# bmsMaster_main.net
KiCad netlist of a schematic drawn in Altium Designer
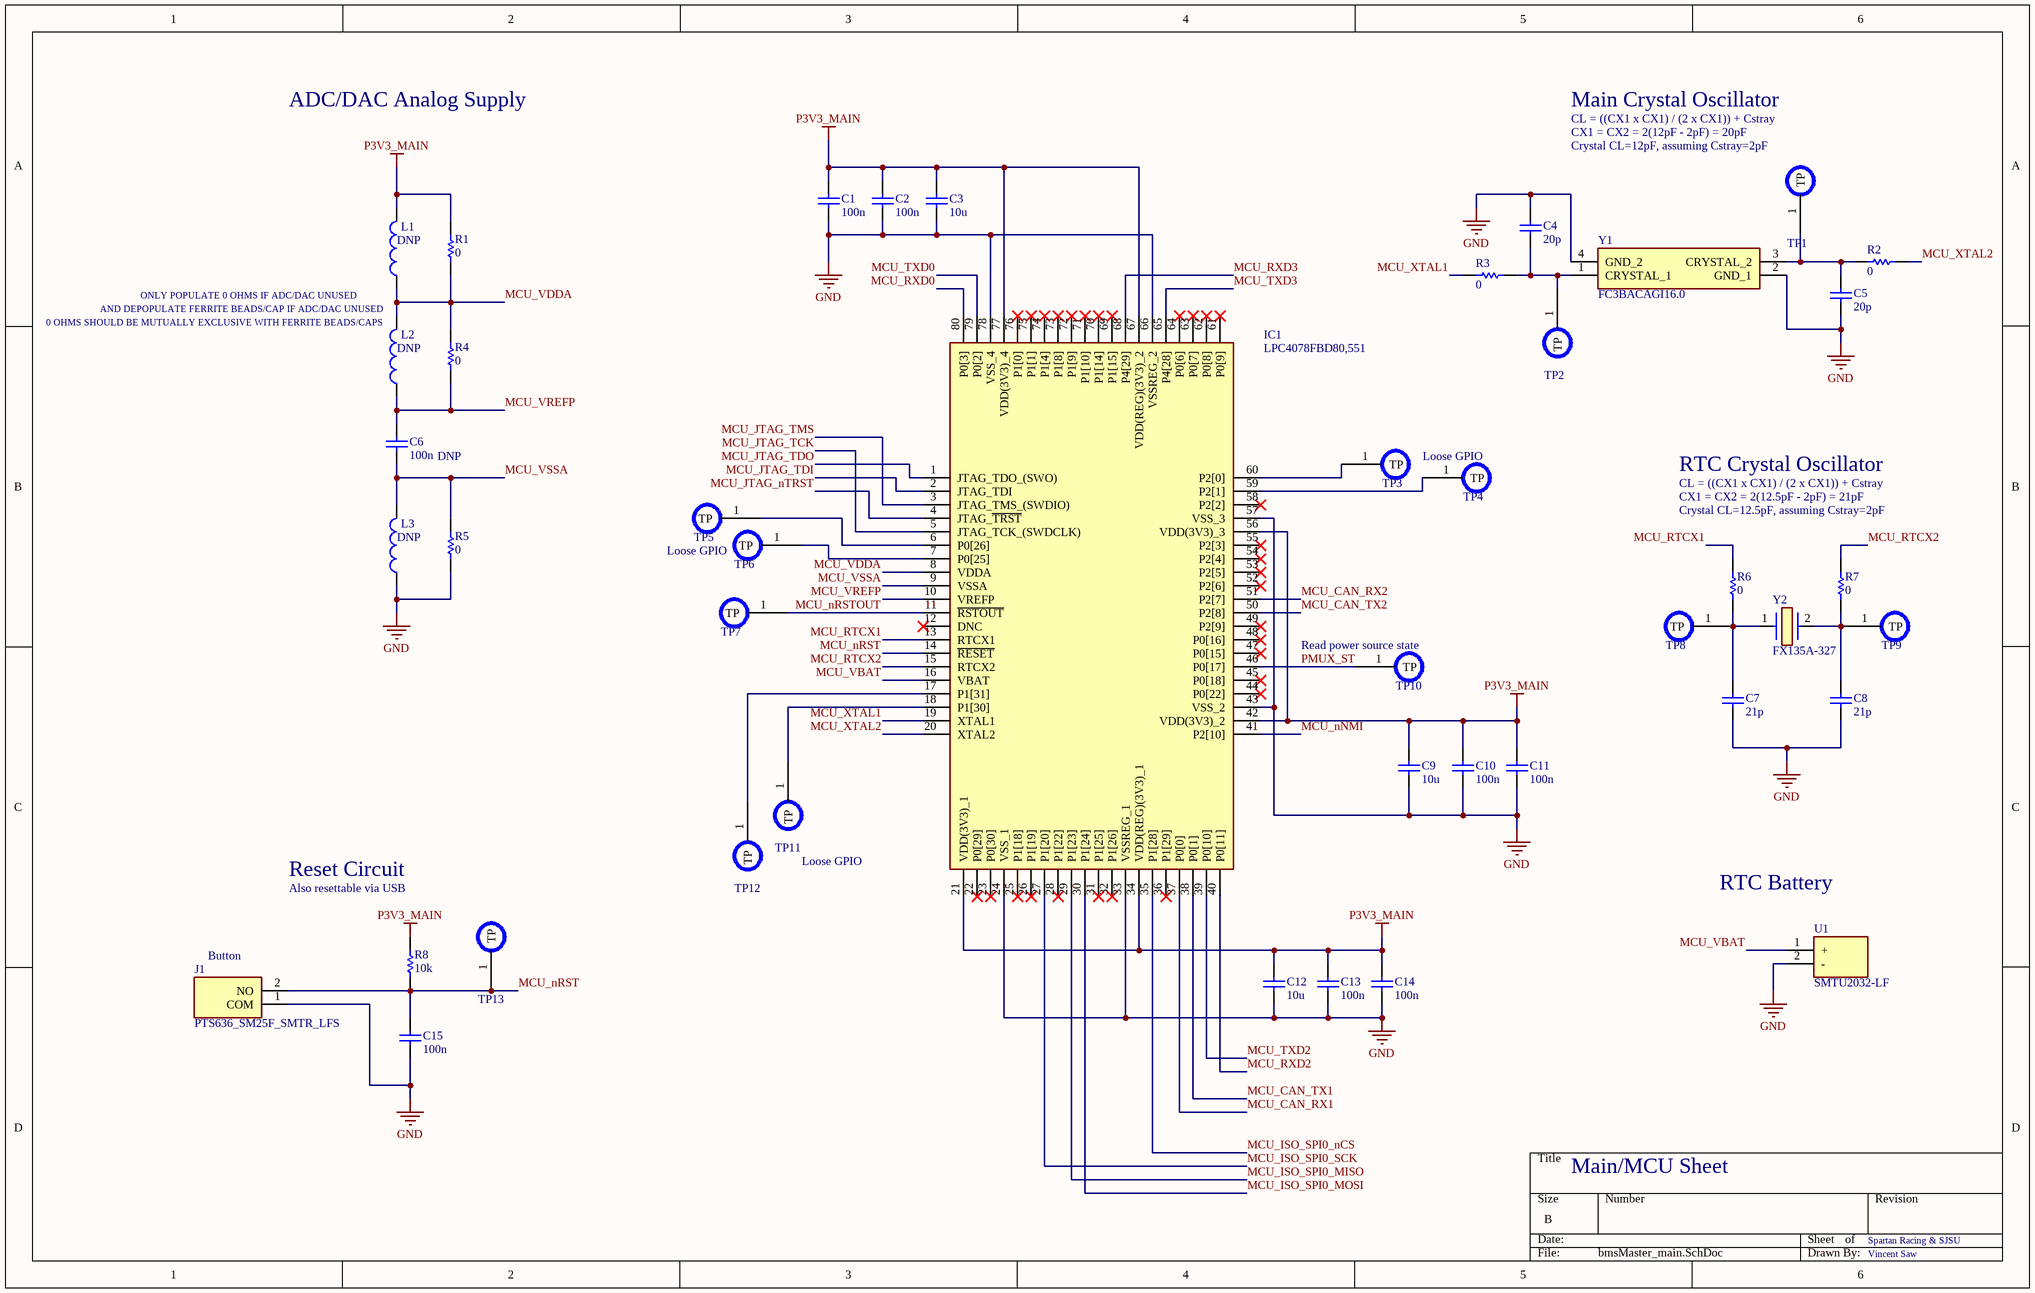
[diagram p0: bmsMaster_main.SchDoc]

(export (version "E")
  (design (tool "Eeschema 10.0.6"))
  (components
    (comp (ref "C1")
      (value "100n")
      (footprint "CAPC1608X90N")
      (description "Capacitor")
      (libsource (lib "Simulation Generic Components") (part "Capacitor"))
    )
    (comp (ref "C2")
      (value "100n")
      (footprint "CAPC1608X90N")
      (description "Capacitor")
      (libsource (lib "Simulation Generic Components") (part "Capacitor"))
    )
    (comp (ref "C3")
      (value "10u")
      (footprint "CAPC1608X90N")
      (description "Capacitor")
      (libsource (lib "Simulation Generic Components") (part "Capacitor"))
    )
    (comp (ref "C4")
      (value "20p")
      (footprint "CAPC1608X90N")
      (description "Capacitor")
      (libsource (lib "Simulation Generic Components") (part "Capacitor"))
    )
    (comp (ref "C5")
      (value "20p")
      (footprint "CAPC1608X90N")
      (description "Capacitor")
      (libsource (lib "Simulation Generic Components") (part "Capacitor"))
    )
    (comp (ref "C6")
      (value "100n")
      (footprint "CAPC1608X90N")
      (description "Capacitor")
      (libsource (lib "Simulation Generic Components") (part "Capacitor"))
    )
    (comp (ref "C7")
      (value "21p")
      (footprint "CAPC1608X90N")
      (description "Capacitor")
      (libsource (lib "Simulation Generic Components") (part "Capacitor"))
    )
    (comp (ref "C8")
      (value "21p")
      (footprint "CAPC1608X90N")
      (description "Capacitor")
      (libsource (lib "Simulation Generic Components") (part "Capacitor"))
    )
    (comp (ref "C9")
      (value "10u")
      (footprint "CAPC1608X90N")
      (description "Capacitor")
      (libsource (lib "Simulation Generic Components") (part "Capacitor"))
    )
    (comp (ref "C10")
      (value "100n")
      (footprint "CAPC1608X90N")
      (description "Capacitor")
      (libsource (lib "Simulation Generic Components") (part "Capacitor"))
    )
    (comp (ref "C11")
      (value "100n")
      (footprint "CAPC1608X90N")
      (description "Capacitor")
      (libsource (lib "Simulation Generic Components") (part "Capacitor"))
    )
    (comp (ref "C12")
      (value "10u")
      (footprint "CAPC1608X90N")
      (description "Capacitor")
      (libsource (lib "Simulation Generic Components") (part "Capacitor"))
    )
    (comp (ref "C13")
      (value "100n")
      (footprint "CAPC1608X90N")
      (description "Capacitor")
      (libsource (lib "Simulation Generic Components") (part "Capacitor"))
    )
    (comp (ref "C14")
      (value "100n")
      (footprint "CAPC1608X90N")
      (description "Capacitor")
      (libsource (lib "Simulation Generic Components") (part "Capacitor"))
    )
    (comp (ref "C15")
      (value "100n")
      (footprint "CAPC1608X90N")
      (description "Capacitor")
      (libsource (lib "Simulation Generic Components") (part "Capacitor"))
    )
    (comp (ref "IC1")
      (value "LPC4078FBD80,551")
      (footprint "SamacSys:QFP50P1400X1400X160-80N")
      (description "Integrated Circuit")
      (fields (field (name "MOUSER PART NUMBER") "771-LPC4078FBD80551"))
      (libsource (lib "*") (part "LPC4078FBD80,551"))
    )
    (comp (ref "J1")
      (value "PTS636_SM25F_SMTR_LFS")
      (footprint "SamacSys:PTS636SM25FSMTRLFS")
      (description "Connector")
      (fields
        (field (name "MANUFACTURER_PART_NUMBER") "PTS636 SM25F SMTR LFS")
        (field (name "MOUSER PART NUMBER") "611-PTS636SM25FSMTRL")
      )
      (libsource (lib "*") (part "PTS636_SM25F_SMTR_LFS"))
    )
    (comp (ref "L1")
      (value "Inductor")
      (footprint "BEADC1608X95N")
      (libsource (lib "Simulation Generic Components") (part "Inductor"))
    )
    (comp (ref "L2")
      (value "Inductor")
      (footprint "BEADC1608X95N")
      (libsource (lib "Simulation Generic Components") (part "Inductor"))
    )
    (comp (ref "L3")
      (value "Inductor")
      (footprint "BEADC1608X95N")
      (libsource (lib "Simulation Generic Components") (part "Inductor"))
    )
    (comp (ref "R1")
      (value "0")
      (footprint "RESC1608X50N")
      (description "Resistor")
      (libsource (lib "Simulation Generic Components") (part "Resistor"))
    )
    (comp (ref "R2")
      (value "0")
      (footprint "RESC1608X50N")
      (description "Resistor")
      (libsource (lib "Simulation Generic Components") (part "Resistor"))
    )
    (comp (ref "R3")
      (value "0")
      (footprint "RESC1608X50N")
      (description "Resistor")
      (libsource (lib "Simulation Generic Components") (part "Resistor"))
    )
    (comp (ref "R4")
      (value "0")
      (footprint "RESC1608X50N")
      (description "Resistor")
      (libsource (lib "Simulation Generic Components") (part "Resistor"))
    )
    (comp (ref "R5")
      (value "0")
      (footprint "RESC1608X50N")
      (description "Resistor")
      (libsource (lib "Simulation Generic Components") (part "Resistor"))
    )
    (comp (ref "R6")
      (value "0")
      (footprint "RESC1608X50N")
      (description "Resistor")
      (libsource (lib "Simulation Generic Components") (part "Resistor"))
    )
    (comp (ref "R7")
      (value "0")
      (footprint "RESC1608X50N")
      (description "Resistor")
      (libsource (lib "Simulation Generic Components") (part "Resistor"))
    )
    (comp (ref "R8")
      (value "10k")
      (footprint "RESC1608X50N")
      (description "Resistor")
      (libsource (lib "Simulation Generic Components") (part "Resistor"))
    )
    (comp (ref "TP1")
      (value "TSTPT")
      (footprint "Testpoint1")
      (libsource (lib "testpoint1") (part "Testpoint1"))
    )
    (comp (ref "TP2")
      (value "TSTPT")
      (footprint "Testpoint1")
      (libsource (lib "testpoint1") (part "Testpoint1"))
    )
    (comp (ref "TP3")
      (value "TSTPT")
      (footprint "Testpoint1")
      (libsource (lib "testpoint1") (part "Testpoint1"))
    )
    (comp (ref "TP4")
      (value "TSTPT")
      (footprint "Testpoint1")
      (libsource (lib "testpoint1") (part "Testpoint1"))
    )
    (comp (ref "TP5")
      (value "TSTPT")
      (footprint "Testpoint1")
      (libsource (lib "testpoint1") (part "Testpoint1"))
    )
    (comp (ref "TP6")
      (value "TSTPT")
      (footprint "Testpoint1")
      (libsource (lib "testpoint1") (part "Testpoint1"))
    )
    (comp (ref "TP7")
      (value "TSTPT")
      (footprint "Testpoint1")
      (libsource (lib "testpoint1") (part "Testpoint1"))
    )
    (comp (ref "TP8")
      (value "TSTPT")
      (footprint "Testpoint1")
      (libsource (lib "testpoint1") (part "Testpoint1"))
    )
    (comp (ref "TP9")
      (value "TSTPT")
      (footprint "Testpoint1")
      (libsource (lib "testpoint1") (part "Testpoint1"))
    )
    (comp (ref "TP10")
      (value "TSTPT")
      (footprint "Testpoint1")
      (libsource (lib "testpoint1") (part "Testpoint1"))
    )
    (comp (ref "TP11")
      (value "TSTPT")
      (footprint "Testpoint1")
      (libsource (lib "testpoint1") (part "Testpoint1"))
    )
    (comp (ref "TP12")
      (value "TSTPT")
      (footprint "Testpoint1")
      (libsource (lib "testpoint1") (part "Testpoint1"))
    )
    (comp (ref "TP13")
      (value "TSTPT")
      (footprint "Testpoint1")
      (libsource (lib "testpoint1") (part "Testpoint1"))
    )
    (comp (ref "U1")
      (value "SMTU2032-LF")
      (footprint "SamacSys:SMTU2032LF")
      (description "Undefined or Miscellaneous")
      (fields (field (name "MOUSER PART NUMBER") "614-SMTU2032-LF"))
      (libsource (lib "*") (part "SMTU2032-LF"))
    )
    (comp (ref "Y1")
      (value "FC3BACAGI16.0")
      (footprint "SamacSys:FC3BACAGI160")
      (description "Crystal or Oscillator")
      (fields (field (name "MOUSER PART NUMBER") "559-FC3BACAGI16.0"))
      (libsource (lib "SamacSys") (part "FC3BACAGI16.0"))
    )
    (comp (ref "Y2")
      (value "FX135A-327")
      (footprint "SamacSys:FX135A327")
      (description "Crystal or Oscillator")
      (fields (field (name "MOUSER PART NUMBER") "559-FX135A-327"))
      (libsource (lib "*") (part "FX135A-327"))
    )
  )
  (nets
    (net (code "1") (name "/MCU_CAN_RX1") (class "Default")
      (node (ref "IC1") (pin "37") (pinfunction "P0[0]_37") (pintype "passive"))
    )
    (net (code "2") (name "/MCU_CAN_RX2") (class "Default")
      (node (ref "IC1") (pin "51") (pinfunction "P2[7]_51") (pintype "passive"))
    )
    (net (code "3") (name "/MCU_CAN_TX1") (class "Default")
      (node (ref "IC1") (pin "38") (pinfunction "P0[1]_38") (pintype "passive"))
    )
    (net (code "4") (name "/MCU_CAN_TX2") (class "Default")
      (node (ref "IC1") (pin "50") (pinfunction "P2[8]_50") (pintype "passive"))
    )
    (net (code "5") (name "/MCU_ISO_SPI0_MISO") (class "Default")
      (node (ref "IC1") (pin "29") (pinfunction "P1[23]_29") (pintype "passive"))
    )
    (net (code "6") (name "/MCU_ISO_SPI0_MOSI") (class "Default")
      (node (ref "IC1") (pin "30") (pinfunction "P1[24]_30") (pintype "passive"))
    )
    (net (code "7") (name "/MCU_ISO_SPI0_SCK") (class "Default")
      (node (ref "IC1") (pin "27") (pinfunction "P1[20]_27") (pintype "passive"))
    )
    (net (code "8") (name "/MCU_ISO_SPI0_nCS") (class "Default")
      (node (ref "IC1") (pin "35") (pinfunction "P1[28]_35") (pintype "passive"))
    )
    (net (code "9") (name "/MCU_JTAG_TCK") (class "Default")
      (node (ref "IC1") (pin "5") (pinfunction "JTAG_TCK_(SWDCLK)_5") (pintype "passive"))
    )
    (net (code "10") (name "/MCU_JTAG_TDI") (class "Default")
      (node (ref "IC1") (pin "2") (pinfunction "JTAG_TDI_2") (pintype "passive"))
    )
    (net (code "11") (name "/MCU_JTAG_TDO") (class "Default")
      (node (ref "IC1") (pin "1") (pinfunction "JTAG_TDO_(SWO)_1") (pintype "passive"))
    )
    (net (code "12") (name "/MCU_JTAG_TMS") (class "Default")
      (node (ref "IC1") (pin "3") (pinfunction "JTAG_TMS_(SWDIO)_3") (pintype "passive"))
    )
    (net (code "13") (name "/MCU_JTAG_nTRST") (class "Default")
      (node (ref "IC1") (pin "4") (pinfunction "JTAG_~{TRST}_4") (pintype "passive"))
    )
    (net (code "14") (name "/MCU_RTCX1") (class "Default")
      (node (ref "IC1") (pin "13") (pinfunction "RTCX1_13") (pintype "passive"))
      (node (ref "R6") (pin "1") (pinfunction "1_1") (pintype "passive"))
    )
    (net (code "15") (name "/MCU_RTCX2") (class "Default")
      (node (ref "IC1") (pin "15") (pinfunction "RTCX2_15") (pintype "passive"))
      (node (ref "R7") (pin "1") (pinfunction "1_1") (pintype "passive"))
    )
    (net (code "16") (name "/MCU_RXD0") (class "Default")
      (node (ref "IC1") (pin "80") (pinfunction "P0[3]_80") (pintype "passive"))
    )
    (net (code "17") (name "/MCU_RXD2") (class "Default")
      (node (ref "IC1") (pin "40") (pinfunction "P0[11]_40") (pintype "passive"))
    )
    (net (code "18") (name "/MCU_RXD3") (class "Default")
      (node (ref "IC1") (pin "68") (pinfunction "P4[29]_68") (pintype "passive"))
    )
    (net (code "19") (name "/MCU_TXD0") (class "Default")
      (node (ref "IC1") (pin "79") (pinfunction "P0[2]_79") (pintype "passive"))
    )
    (net (code "20") (name "/MCU_TXD2") (class "Default")
      (node (ref "IC1") (pin "39") (pinfunction "P0[10]_39") (pintype "passive"))
    )
    (net (code "21") (name "/MCU_TXD3") (class "Default")
      (node (ref "IC1") (pin "65") (pinfunction "P4[28]_65") (pintype "passive"))
    )
    (net (code "22") (name "/MCU_VBAT") (class "Default")
      (node (ref "IC1") (pin "16") (pinfunction "VBAT_16") (pintype "passive"))
      (node (ref "U1") (pin "1") (pinfunction "+_1") (pintype "passive"))
    )
    (net (code "23") (name "/MCU_VDDA") (class "Default")
      (node (ref "IC1") (pin "8") (pinfunction "VDDA_8") (pintype "passive"))
      (node (ref "L1") (pin "1") (pinfunction "1_1") (pintype "passive"))
      (node (ref "L2") (pin "2") (pinfunction "2_2") (pintype "passive"))
      (node (ref "R1") (pin "1") (pinfunction "1_1") (pintype "passive"))
      (node (ref "R4") (pin "2") (pinfunction "2_2") (pintype "passive"))
    )
    (net (code "24") (name "/MCU_VREFP") (class "Default")
      (node (ref "C6") (pin "2") (pinfunction "2_2") (pintype "passive"))
      (node (ref "IC1") (pin "10") (pinfunction "VREFP_10") (pintype "passive"))
      (node (ref "L2") (pin "1") (pinfunction "1_1") (pintype "passive"))
      (node (ref "R4") (pin "1") (pinfunction "1_1") (pintype "passive"))
    )
    (net (code "25") (name "/MCU_VSSA") (class "Default")
      (node (ref "C6") (pin "1") (pinfunction "1_1") (pintype "passive"))
      (node (ref "IC1") (pin "9") (pinfunction "VSSA_9") (pintype "passive"))
      (node (ref "L3") (pin "2") (pinfunction "2_2") (pintype "passive"))
      (node (ref "R5") (pin "2") (pinfunction "2_2") (pintype "passive"))
    )
    (net (code "26") (name "/MCU_XTAL1") (class "Default")
      (node (ref "IC1") (pin "19") (pinfunction "XTAL1_19") (pintype "passive"))
      (node (ref "R3") (pin "2") (pinfunction "2_2") (pintype "passive"))
    )
    (net (code "27") (name "/MCU_XTAL2") (class "Default")
      (node (ref "IC1") (pin "20") (pinfunction "XTAL2_20") (pintype "passive"))
      (node (ref "R2") (pin "1") (pinfunction "1_1") (pintype "passive"))
    )
    (net (code "28") (name "/MCU_nNMI") (class "Default")
      (node (ref "IC1") (pin "41") (pinfunction "P2[10]_41") (pintype "passive"))
    )
    (net (code "29") (name "/MCU_nRST") (class "Default")
      (node (ref "C15") (pin "2") (pinfunction "2_2") (pintype "passive"))
      (node (ref "IC1") (pin "14") (pinfunction "~{RESET}_14") (pintype "passive"))
      (node (ref "J1") (pin "2") (pinfunction "NO_2") (pintype "passive"))
      (node (ref "R8") (pin "1") (pinfunction "1_1") (pintype "passive"))
      (node (ref "TP13") (pin "1") (pinfunction "TP_1") (pintype "passive"))
    )
    (net (code "30") (name "/MCU_nRSTOUT") (class "Default")
      (node (ref "IC1") (pin "11") (pinfunction "~{RSTOUT}_11") (pintype "passive"))
      (node (ref "TP7") (pin "1") (pinfunction "TP_1") (pintype "passive"))
    )
    (net (code "31") (name "/PMUX_ST") (class "Default")
      (node (ref "IC1") (pin "46") (pinfunction "P0[17]_46") (pintype "passive"))
      (node (ref "TP10") (pin "1") (pinfunction "TP_1") (pintype "passive"))
    )
    (net (code "32") (name "GND") (class "Default")
      (node (ref "C1") (pin "1") (pinfunction "1_1") (pintype "passive"))
      (node (ref "C10") (pin "1") (pinfunction "1_1") (pintype "passive"))
      (node (ref "C11") (pin "1") (pinfunction "1_1") (pintype "passive"))
      (node (ref "C12") (pin "1") (pinfunction "1_1") (pintype "passive"))
      (node (ref "C13") (pin "1") (pinfunction "1_1") (pintype "passive"))
      (node (ref "C14") (pin "1") (pinfunction "1_1") (pintype "passive"))
      (node (ref "C15") (pin "1") (pinfunction "1_1") (pintype "passive"))
      (node (ref "C2") (pin "1") (pinfunction "1_1") (pintype "passive"))
      (node (ref "C3") (pin "1") (pinfunction "1_1") (pintype "passive"))
      (node (ref "C4") (pin "2") (pinfunction "2_2") (pintype "passive"))
      (node (ref "C5") (pin "1") (pinfunction "1_1") (pintype "passive"))
      (node (ref "C7") (pin "1") (pinfunction "1_1") (pintype "passive"))
      (node (ref "C8") (pin "1") (pinfunction "1_1") (pintype "passive"))
      (node (ref "C9") (pin "1") (pinfunction "1_1") (pintype "passive"))
      (node (ref "IC1") (pin "24") (pinfunction "VSS_1_24") (pintype "passive"))
      (node (ref "IC1") (pin "33") (pinfunction "VSSREG_1_33") (pintype "passive"))
      (node (ref "IC1") (pin "43") (pinfunction "VSS_2_43") (pintype "passive"))
      (node (ref "IC1") (pin "57") (pinfunction "VSS_3_57") (pintype "passive"))
      (node (ref "IC1") (pin "66") (pinfunction "VSSREG_2_66") (pintype "passive"))
      (node (ref "IC1") (pin "78") (pinfunction "VSS_4_78") (pintype "passive"))
      (node (ref "J1") (pin "1") (pinfunction "COM_1") (pintype "passive"))
      (node (ref "L3") (pin "1") (pinfunction "1_1") (pintype "passive"))
      (node (ref "R5") (pin "1") (pinfunction "1_1") (pintype "passive"))
      (node (ref "U1") (pin "2") (pinfunction "-_2") (pintype "passive"))
      (node (ref "Y1") (pin "2") (pinfunction "GND_1_2") (pintype "passive"))
      (node (ref "Y1") (pin "4") (pinfunction "GND_2_4") (pintype "passive"))
    )
    (net (code "33") (name "Net-(IC1-P0[25])") (class "Default")
      (node (ref "IC1") (pin "7") (pinfunction "P0[25]_7") (pintype "passive"))
      (node (ref "TP6") (pin "1") (pinfunction "TP_1") (pintype "passive"))
    )
    (net (code "34") (name "Net-(IC1-P0[26])") (class "Default")
      (node (ref "IC1") (pin "6") (pinfunction "P0[26]_6") (pintype "passive"))
      (node (ref "TP5") (pin "1") (pinfunction "TP_1") (pintype "passive"))
    )
    (net (code "35") (name "Net-(IC1-P1[30])") (class "Default")
      (node (ref "IC1") (pin "18") (pinfunction "P1[30]_18") (pintype "passive"))
      (node (ref "TP11") (pin "1") (pinfunction "TP_1") (pintype "passive"))
    )
    (net (code "36") (name "Net-(IC1-P1[31])") (class "Default")
      (node (ref "IC1") (pin "17") (pinfunction "P1[31]_17") (pintype "passive"))
      (node (ref "TP12") (pin "1") (pinfunction "TP_1") (pintype "passive"))
    )
    (net (code "37") (name "Net-(IC1-P2[0])") (class "Default")
      (node (ref "IC1") (pin "60") (pinfunction "P2[0]_60") (pintype "passive"))
      (node (ref "TP3") (pin "1") (pinfunction "TP_1") (pintype "passive"))
    )
    (net (code "38") (name "Net-(IC1-P2[1])") (class "Default")
      (node (ref "IC1") (pin "59") (pinfunction "P2[1]_59") (pintype "passive"))
      (node (ref "TP4") (pin "1") (pinfunction "TP_1") (pintype "passive"))
    )
    (net (code "39") (name "Net-(TP1-TP)") (class "Default")
      (node (ref "C5") (pin "2") (pinfunction "2_2") (pintype "passive"))
      (node (ref "R2") (pin "2") (pinfunction "2_2") (pintype "passive"))
      (node (ref "TP1") (pin "1") (pinfunction "TP_1") (pintype "passive"))
      (node (ref "Y1") (pin "3") (pinfunction "CRYSTAL_2_3") (pintype "passive"))
    )
    (net (code "40") (name "Net-(TP2-TP)") (class "Default")
      (node (ref "C4") (pin "1") (pinfunction "1_1") (pintype "passive"))
      (node (ref "R3") (pin "1") (pinfunction "1_1") (pintype "passive"))
      (node (ref "TP2") (pin "1") (pinfunction "TP_1") (pintype "passive"))
      (node (ref "Y1") (pin "1") (pinfunction "CRYSTAL_1_1") (pintype "passive"))
    )
    (net (code "41") (name "Net-(TP8-TP)") (class "Default")
      (node (ref "C7") (pin "2") (pinfunction "2_2") (pintype "passive"))
      (node (ref "R6") (pin "2") (pinfunction "2_2") (pintype "passive"))
      (node (ref "TP8") (pin "1") (pinfunction "TP_1") (pintype "passive"))
      (node (ref "Y2") (pin "1") (pinfunction "1_1") (pintype "passive"))
    )
    (net (code "42") (name "Net-(TP9-TP)") (class "Default")
      (node (ref "C8") (pin "2") (pinfunction "2_2") (pintype "passive"))
      (node (ref "R7") (pin "2") (pinfunction "2_2") (pintype "passive"))
      (node (ref "TP9") (pin "1") (pinfunction "TP_1") (pintype "passive"))
      (node (ref "Y2") (pin "2") (pinfunction "2_2") (pintype "passive"))
    )
    (net (code "43") (name "P3V3_MAIN") (class "Default")
      (node (ref "C1") (pin "2") (pinfunction "2_2") (pintype "passive"))
      (node (ref "C10") (pin "2") (pinfunction "2_2") (pintype "passive"))
      (node (ref "C11") (pin "2") (pinfunction "2_2") (pintype "passive"))
      (node (ref "C12") (pin "2") (pinfunction "2_2") (pintype "passive"))
      (node (ref "C13") (pin "2") (pinfunction "2_2") (pintype "passive"))
      (node (ref "C14") (pin "2") (pinfunction "2_2") (pintype "passive"))
      (node (ref "C2") (pin "2") (pinfunction "2_2") (pintype "passive"))
      (node (ref "C3") (pin "2") (pinfunction "2_2") (pintype "passive"))
      (node (ref "C9") (pin "2") (pinfunction "2_2") (pintype "passive"))
      (node (ref "IC1") (pin "21") (pinfunction "VDD(3V3)_1_21") (pintype "passive"))
      (node (ref "IC1") (pin "34") (pinfunction "VDD(REG)(3V3)_1_34") (pintype "passive"))
      (node (ref "IC1") (pin "42") (pinfunction "VDD(3V3)_2_42") (pintype "passive"))
      (node (ref "IC1") (pin "56") (pinfunction "VDD(3V3)_3_56") (pintype "passive"))
      (node (ref "IC1") (pin "67") (pinfunction "VDD(REG)(3V3)_2_67") (pintype "passive"))
      (node (ref "IC1") (pin "77") (pinfunction "VDD(3V3)_4_77") (pintype "passive"))
      (node (ref "L1") (pin "2") (pinfunction "2_2") (pintype "passive"))
      (node (ref "R1") (pin "2") (pinfunction "2_2") (pintype "passive"))
      (node (ref "R8") (pin "2") (pinfunction "2_2") (pintype "passive"))
    )
    (net (code "44") (name "unconnected-(IC1-DNC-Pad12)") (class "Default")
      (node (ref "IC1") (pin "12") (pinfunction "DNC_12") (pintype "passive+no_connect"))
    )
    (net (code "45") (name "unconnected-(IC1-P0[6]-Pad64)") (class "Default")
      (node (ref "IC1") (pin "64") (pinfunction "P0[6]_64") (pintype "passive+no_connect"))
    )
    (net (code "46") (name "unconnected-(IC1-P0[7]-Pad63)") (class "Default")
      (node (ref "IC1") (pin "63") (pinfunction "P0[7]_63") (pintype "passive+no_connect"))
    )
    (net (code "47") (name "unconnected-(IC1-P0[8]-Pad62)") (class "Default")
      (node (ref "IC1") (pin "62") (pinfunction "P0[8]_62") (pintype "passive+no_connect"))
    )
    (net (code "48") (name "unconnected-(IC1-P0[9]-Pad61)") (class "Default")
      (node (ref "IC1") (pin "61") (pinfunction "P0[9]_61") (pintype "passive+no_connect"))
    )
    (net (code "49") (name "unconnected-(IC1-P0[15]-Pad47)") (class "Default")
      (node (ref "IC1") (pin "47") (pinfunction "P0[15]_47") (pintype "passive+no_connect"))
    )
    (net (code "50") (name "unconnected-(IC1-P0[16]-Pad48)") (class "Default")
      (node (ref "IC1") (pin "48") (pinfunction "P0[16]_48") (pintype "passive+no_connect"))
    )
    (net (code "51") (name "unconnected-(IC1-P0[18]-Pad45)") (class "Default")
      (node (ref "IC1") (pin "45") (pinfunction "P0[18]_45") (pintype "passive+no_connect"))
    )
    (net (code "52") (name "unconnected-(IC1-P0[22]-Pad44)") (class "Default")
      (node (ref "IC1") (pin "44") (pinfunction "P0[22]_44") (pintype "passive+no_connect"))
    )
    (net (code "53") (name "unconnected-(IC1-P0[29]-Pad22)") (class "Default")
      (node (ref "IC1") (pin "22") (pinfunction "P0[29]_22") (pintype "passive+no_connect"))
    )
    (net (code "54") (name "unconnected-(IC1-P0[30]-Pad23)") (class "Default")
      (node (ref "IC1") (pin "23") (pinfunction "P0[30]_23") (pintype "passive+no_connect"))
    )
    (net (code "55") (name "unconnected-(IC1-P1[0]-Pad76)") (class "Default")
      (node (ref "IC1") (pin "76") (pinfunction "P1[0]_76") (pintype "passive+no_connect"))
    )
    (net (code "56") (name "unconnected-(IC1-P1[1]-Pad75)") (class "Default")
      (node (ref "IC1") (pin "75") (pinfunction "P1[1]_75") (pintype "passive+no_connect"))
    )
    (net (code "57") (name "unconnected-(IC1-P1[4]-Pad74)") (class "Default")
      (node (ref "IC1") (pin "74") (pinfunction "P1[4]_74") (pintype "passive+no_connect"))
    )
    (net (code "58") (name "unconnected-(IC1-P1[8]-Pad73)") (class "Default")
      (node (ref "IC1") (pin "73") (pinfunction "P1[8]_73") (pintype "passive+no_connect"))
    )
    (net (code "59") (name "unconnected-(IC1-P1[9]-Pad72)") (class "Default")
      (node (ref "IC1") (pin "72") (pinfunction "P1[9]_72") (pintype "passive+no_connect"))
    )
    (net (code "60") (name "unconnected-(IC1-P1[10]-Pad71)") (class "Default")
      (node (ref "IC1") (pin "71") (pinfunction "P1[10]_71") (pintype "passive+no_connect"))
    )
    (net (code "61") (name "unconnected-(IC1-P1[14]-Pad70)") (class "Default")
      (node (ref "IC1") (pin "70") (pinfunction "P1[14]_70") (pintype "passive+no_connect"))
    )
    (net (code "62") (name "unconnected-(IC1-P1[15]-Pad69)") (class "Default")
      (node (ref "IC1") (pin "69") (pinfunction "P1[15]_69") (pintype "passive+no_connect"))
    )
    (net (code "63") (name "unconnected-(IC1-P1[18]-Pad25)") (class "Default")
      (node (ref "IC1") (pin "25") (pinfunction "P1[18]_25") (pintype "passive+no_connect"))
    )
    (net (code "64") (name "unconnected-(IC1-P1[19]-Pad26)") (class "Default")
      (node (ref "IC1") (pin "26") (pinfunction "P1[19]_26") (pintype "passive+no_connect"))
    )
    (net (code "65") (name "unconnected-(IC1-P1[22]-Pad28)") (class "Default")
      (node (ref "IC1") (pin "28") (pinfunction "P1[22]_28") (pintype "passive+no_connect"))
    )
    (net (code "66") (name "unconnected-(IC1-P1[25]-Pad31)") (class "Default")
      (node (ref "IC1") (pin "31") (pinfunction "P1[25]_31") (pintype "passive+no_connect"))
    )
    (net (code "67") (name "unconnected-(IC1-P1[26]-Pad32)") (class "Default")
      (node (ref "IC1") (pin "32") (pinfunction "P1[26]_32") (pintype "passive+no_connect"))
    )
    (net (code "68") (name "unconnected-(IC1-P1[29]-Pad36)") (class "Default")
      (node (ref "IC1") (pin "36") (pinfunction "P1[29]_36") (pintype "passive+no_connect"))
    )
    (net (code "69") (name "unconnected-(IC1-P2[2]-Pad58)") (class "Default")
      (node (ref "IC1") (pin "58") (pinfunction "P2[2]_58") (pintype "passive+no_connect"))
    )
    (net (code "70") (name "unconnected-(IC1-P2[3]-Pad55)") (class "Default")
      (node (ref "IC1") (pin "55") (pinfunction "P2[3]_55") (pintype "passive+no_connect"))
    )
    (net (code "71") (name "unconnected-(IC1-P2[4]-Pad54)") (class "Default")
      (node (ref "IC1") (pin "54") (pinfunction "P2[4]_54") (pintype "passive+no_connect"))
    )
    (net (code "72") (name "unconnected-(IC1-P2[5]-Pad53)") (class "Default")
      (node (ref "IC1") (pin "53") (pinfunction "P2[5]_53") (pintype "passive+no_connect"))
    )
    (net (code "73") (name "unconnected-(IC1-P2[6]-Pad52)") (class "Default")
      (node (ref "IC1") (pin "52") (pinfunction "P2[6]_52") (pintype "passive+no_connect"))
    )
    (net (code "74") (name "unconnected-(IC1-P2[9]-Pad49)") (class "Default")
      (node (ref "IC1") (pin "49") (pinfunction "P2[9]_49") (pintype "passive+no_connect"))
    )
  )
)
